# CTS_Teensy_Board.net
KiCad netlist of a schematic drawn in EAGLE
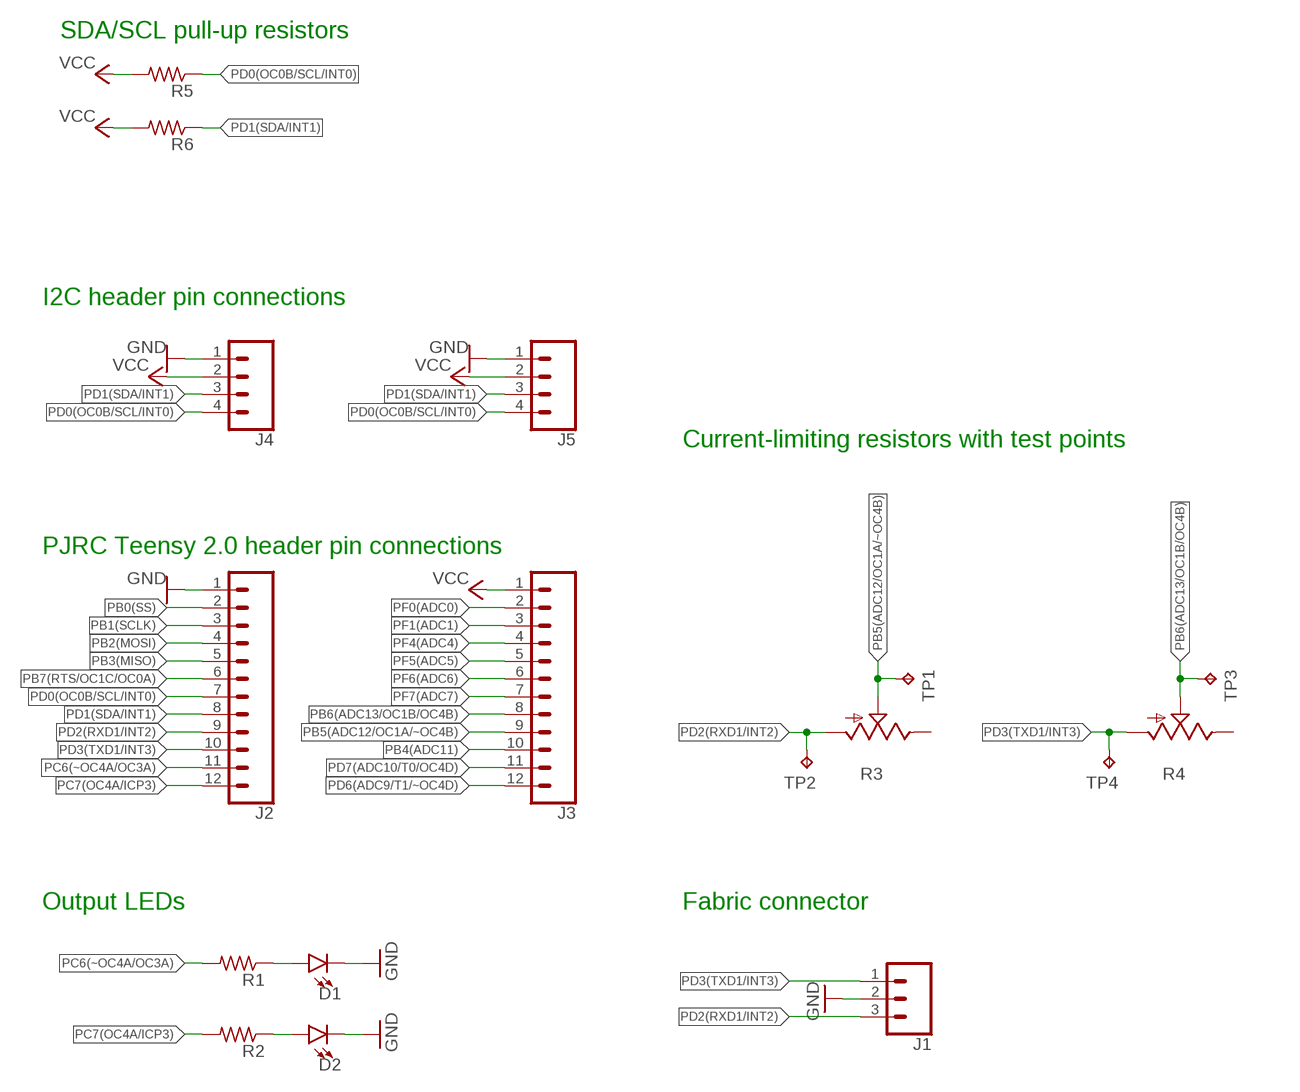
[diagram p0: schematic, sheet 1]

(export (version "E")
  (design (tool "Eeschema 10.0.6"))
  (components
    (comp (ref "D1")
      (value "LED3MM")
      (footprint "eagle-import:LED_3MM")
      (libsource (lib "eagle-import") (part "LED3MM"))
    )
    (comp (ref "D2")
      (value "LED3MM")
      (footprint "eagle-import:LED_3MM")
      (libsource (lib "eagle-import") (part "LED3MM"))
    )
    (comp (ref "J1")
      (value "CONN_03POLAR")
      (footprint "eagle-import:MOLEX-1X3")
      (libsource (lib "eagle-import") (part "CONN_03POLAR"))
    )
    (comp (ref "J2")
      (value "CONN_12")
      (footprint "eagle-import:1X12")
      (libsource (lib "eagle-import") (part "CONN_12"))
    )
    (comp (ref "J3")
      (value "CONN_12")
      (footprint "eagle-import:1X12")
      (libsource (lib "eagle-import") (part "CONN_12"))
    )
    (comp (ref "J4")
      (value "CONN_04")
      (footprint "eagle-import:1X04")
      (libsource (lib "eagle-import") (part "CONN_04"))
    )
    (comp (ref "J5")
      (value "CONN_04")
      (footprint "eagle-import:1X04")
      (libsource (lib "eagle-import") (part "CONN_04"))
    )
    (comp (ref "R1")
      (value "R-US_0204/7")
      (footprint "eagle-import:0204_7")
      (libsource (lib "eagle-import") (part "R-US_0204/7"))
    )
    (comp (ref "R2")
      (value "R-US_0204/7")
      (footprint "eagle-import:0204_7")
      (libsource (lib "eagle-import") (part "R-US_0204/7"))
    )
    (comp (ref "R3")
      (value "TRIM_US-B90P")
      (footprint "eagle-import:SP19L")
      (libsource (lib "eagle-import") (part "TRIM_US-B90P"))
    )
    (comp (ref "R4")
      (value "TRIM_US-B90P")
      (footprint "eagle-import:SP19L")
      (libsource (lib "eagle-import") (part "TRIM_US-B90P"))
    )
    (comp (ref "R5")
      (value "R-US_0204/7")
      (footprint "eagle-import:0204_7")
      (libsource (lib "eagle-import") (part "R-US_0204/7"))
    )
    (comp (ref "R6")
      (value "R-US_0204/7")
      (footprint "eagle-import:0204_7")
      (libsource (lib "eagle-import") (part "R-US_0204/7"))
    )
    (comp (ref "TP1")
      (value "TPTP18R")
      (footprint "eagle-import:TP18R")
      (libsource (lib "eagle-import") (part "TPTP18R"))
    )
    (comp (ref "TP2")
      (value "TPTP18R")
      (footprint "eagle-import:TP18R")
      (libsource (lib "eagle-import") (part "TPTP18R"))
    )
    (comp (ref "TP3")
      (value "TPTP18R")
      (footprint "eagle-import:TP18R")
      (libsource (lib "eagle-import") (part "TPTP18R"))
    )
    (comp (ref "TP4")
      (value "TPTP18R")
      (footprint "eagle-import:TP18R")
      (libsource (lib "eagle-import") (part "TPTP18R"))
    )
  )
  (nets
    (net (code "1") (name "/PB5(ADC12{slash}OC1A{slash}~{OC4B})") (class "Default")
      (node (ref "J3") (pin "9") (pinfunction "9_9") (pintype "passive"))
      (node (ref "R3") (pin "S") (pinfunction "S_S") (pintype "passive"))
      (node (ref "TP1") (pin "TP") (pinfunction "TP_TP") (pintype "input"))
    )
    (net (code "2") (name "/PC6(~{OC4A{slash}OC3A})") (class "Default")
      (node (ref "J2") (pin "11") (pinfunction "11_11") (pintype "passive"))
      (node (ref "R1") (pin "2") (pinfunction "2_2") (pintype "passive"))
    )
    (net (code "3") (name "/PD6(ADC9{slash}T1{slash}~{OC4D})") (class "Default")
      (node (ref "J3") (pin "12") (pinfunction "12_12") (pintype "passive"))
    )
    (net (code "4") (name "GND") (class "Default")
      (node (ref "D1") (pin "K") (pinfunction "C_K") (pintype "passive"))
      (node (ref "D2") (pin "K") (pinfunction "C_K") (pintype "passive"))
      (node (ref "J1") (pin "2") (pinfunction "2_2") (pintype "passive"))
      (node (ref "J2") (pin "1") (pinfunction "1_1") (pintype "passive"))
      (node (ref "J4") (pin "1") (pinfunction "1_1") (pintype "passive"))
      (node (ref "J5") (pin "1") (pinfunction "1_1") (pintype "passive"))
    )
    (net (code "5") (name "Net-(D1-PadA)") (class "Default")
      (node (ref "D1") (pin "A") (pinfunction "A_A") (pintype "passive"))
      (node (ref "R1") (pin "1") (pinfunction "1_1") (pintype "passive"))
    )
    (net (code "6") (name "Net-(D2-PadA)") (class "Default")
      (node (ref "D2") (pin "A") (pinfunction "A_A") (pintype "passive"))
      (node (ref "R2") (pin "1") (pinfunction "1_1") (pintype "passive"))
    )
    (net (code "7") (name "PB0(SS)") (class "Default")
      (node (ref "J2") (pin "2") (pinfunction "2_2") (pintype "passive"))
    )
    (net (code "8") (name "PB1(SCLK)") (class "Default")
      (node (ref "J2") (pin "3") (pinfunction "3_3") (pintype "passive"))
    )
    (net (code "9") (name "PB2(MOSI)") (class "Default")
      (node (ref "J2") (pin "4") (pinfunction "4_4") (pintype "passive"))
    )
    (net (code "10") (name "PB3(MISO)") (class "Default")
      (node (ref "J2") (pin "5") (pinfunction "5_5") (pintype "passive"))
    )
    (net (code "11") (name "PB4(ADC11)") (class "Default")
      (node (ref "J3") (pin "10") (pinfunction "10_10") (pintype "passive"))
    )
    (net (code "12") (name "PB6(ADC13{slash}OC1B{slash}OC4B)") (class "Default")
      (node (ref "J3") (pin "8") (pinfunction "8_8") (pintype "passive"))
      (node (ref "R4") (pin "S") (pinfunction "S_S") (pintype "passive"))
      (node (ref "TP3") (pin "TP") (pinfunction "TP_TP") (pintype "input"))
    )
    (net (code "13") (name "PB7(RTS{slash}OC1C{slash}OC0A)") (class "Default")
      (node (ref "J2") (pin "6") (pinfunction "6_6") (pintype "passive"))
    )
    (net (code "14") (name "PC7(OC4A{slash}ICP3)") (class "Default")
      (node (ref "J2") (pin "12") (pinfunction "12_12") (pintype "passive"))
      (node (ref "R2") (pin "2") (pinfunction "2_2") (pintype "passive"))
    )
    (net (code "15") (name "PD0(OC0B{slash}SCL{slash}INT0)") (class "Default")
      (node (ref "J2") (pin "7") (pinfunction "7_7") (pintype "passive"))
      (node (ref "J4") (pin "4") (pinfunction "4_4") (pintype "passive"))
      (node (ref "J5") (pin "4") (pinfunction "4_4") (pintype "passive"))
      (node (ref "R5") (pin "1") (pinfunction "1_1") (pintype "passive"))
    )
    (net (code "16") (name "PD1(SDA{slash}INT1)") (class "Default")
      (node (ref "J2") (pin "8") (pinfunction "8_8") (pintype "passive"))
      (node (ref "J4") (pin "3") (pinfunction "3_3") (pintype "passive"))
      (node (ref "J5") (pin "3") (pinfunction "3_3") (pintype "passive"))
      (node (ref "R6") (pin "1") (pinfunction "1_1") (pintype "passive"))
    )
    (net (code "17") (name "PD2(RXD1{slash}INT2)") (class "Default")
      (node (ref "J1") (pin "3") (pinfunction "3_3") (pintype "passive"))
      (node (ref "J2") (pin "9") (pinfunction "9_9") (pintype "passive"))
      (node (ref "R3") (pin "A") (pinfunction "A_A") (pintype "passive"))
      (node (ref "TP2") (pin "TP") (pinfunction "TP_TP") (pintype "input"))
    )
    (net (code "18") (name "PD3(TXD1{slash}INT3)") (class "Default")
      (node (ref "J1") (pin "1") (pinfunction "1_1") (pintype "passive"))
      (node (ref "J2") (pin "10") (pinfunction "10_10") (pintype "passive"))
      (node (ref "R4") (pin "A") (pinfunction "A_A") (pintype "passive"))
      (node (ref "TP4") (pin "TP") (pinfunction "TP_TP") (pintype "input"))
    )
    (net (code "19") (name "PD7(ADC10{slash}T0{slash}OC4D)") (class "Default")
      (node (ref "J3") (pin "11") (pinfunction "11_11") (pintype "passive"))
    )
    (net (code "20") (name "PF0(ADC0)") (class "Default")
      (node (ref "J3") (pin "2") (pinfunction "2_2") (pintype "passive"))
    )
    (net (code "21") (name "PF1(ADC1)") (class "Default")
      (node (ref "J3") (pin "3") (pinfunction "3_3") (pintype "passive"))
    )
    (net (code "22") (name "PF4(ADC4)") (class "Default")
      (node (ref "J3") (pin "4") (pinfunction "4_4") (pintype "passive"))
    )
    (net (code "23") (name "PF5(ADC5)") (class "Default")
      (node (ref "J3") (pin "5") (pinfunction "5_5") (pintype "passive"))
    )
    (net (code "24") (name "PF6(ADC6)") (class "Default")
      (node (ref "J3") (pin "6") (pinfunction "6_6") (pintype "passive"))
    )
    (net (code "25") (name "PF7(ADC7)") (class "Default")
      (node (ref "J3") (pin "7") (pinfunction "7_7") (pintype "passive"))
    )
    (net (code "26") (name "VCC") (class "Default")
      (node (ref "J3") (pin "1") (pinfunction "1_1") (pintype "passive"))
      (node (ref "J4") (pin "2") (pinfunction "2_2") (pintype "passive"))
      (node (ref "J5") (pin "2") (pinfunction "2_2") (pintype "passive"))
      (node (ref "R5") (pin "2") (pinfunction "2_2") (pintype "passive"))
      (node (ref "R6") (pin "2") (pinfunction "2_2") (pintype "passive"))
    )
    (net (code "27") (name "unconnected-(R3-PadE)") (class "Default")
      (node (ref "R3") (pin "E") (pinfunction "E_E") (pintype "passive"))
    )
    (net (code "28") (name "unconnected-(R4-PadE)") (class "Default")
      (node (ref "R4") (pin "E") (pinfunction "E_E") (pintype "passive"))
    )
  )
)
